# Power.net
KiCad netlist of a schematic drawn in Altium Designer
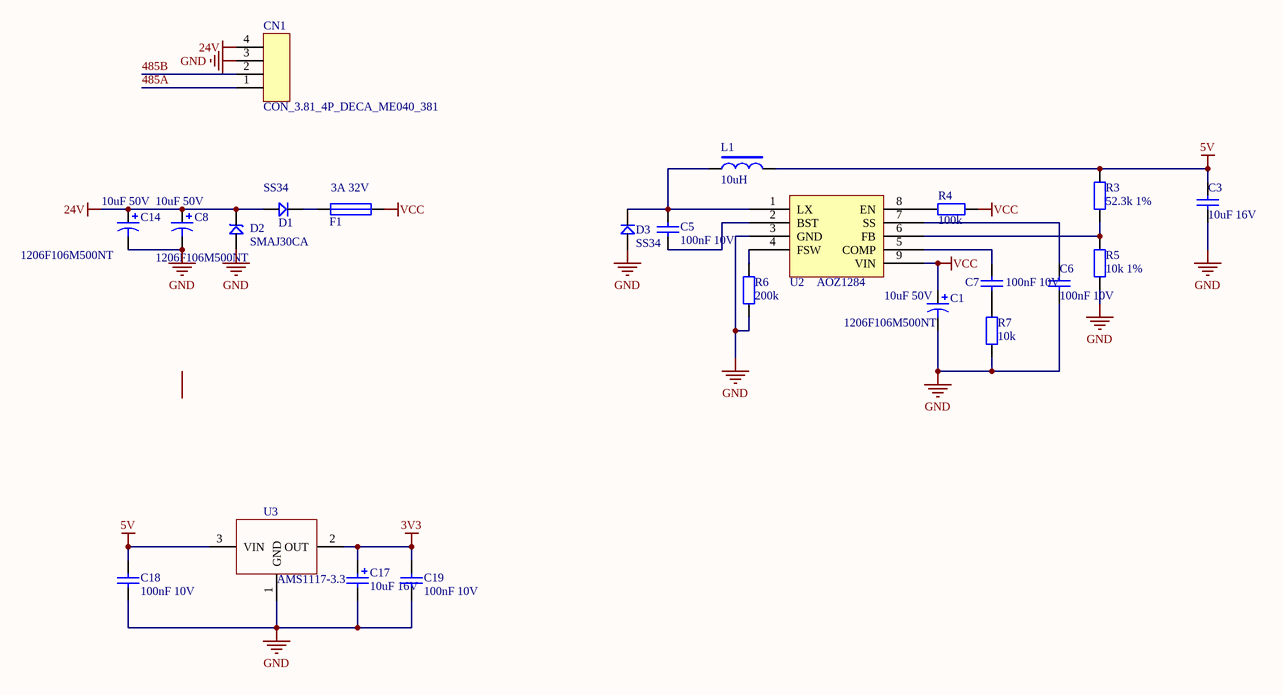
[diagram p0: Power.SchDoc]

(export (version "E")
  (design (tool "Eeschema 10.0.6"))
  (components
    (comp (ref "C1")
      (value "10uF 50V")
      (footprint "C1206")
      (description "贴片陶瓷电容")
      (fields (field (name "蜜称") "1206F106M500NT") (field (name "PUBLISHER") "Altium Limited"))
      (libsource (lib "Skcl") (part "Cap Pol1"))
    )
    (comp (ref "C3")
      (value "10uF 16V")
      (footprint "C1206")
      (description "贴片陶瓷电容")
      (libsource (lib "stm32_s") (part "CAP"))
    )
    (comp (ref "C5") (value "100nF 10V") (footprint "C0603") (libsource (lib "stm32_s") (part "CAP")))
    (comp (ref "C6") (value "100nF 10V") (footprint "C0603") (libsource (lib "stm32_s") (part "CAP")))
    (comp (ref "C7") (value "100nF 10V") (footprint "C0603") (libsource (lib "stm32_s") (part "CAP")))
    (comp (ref "C8")
      (value "10uF 50V")
      (footprint "C1206")
      (description "贴片陶瓷电容")
      (fields (field (name "蜜称") "1206F106M500NT") (field (name "PUBLISHER") "Altium Limited"))
      (libsource (lib "Skcl") (part "Cap Pol1"))
    )
    (comp (ref "C14")
      (value "10uF 50V")
      (footprint "C1206")
      (description "贴片陶瓷电容")
      (fields (field (name "蜜称") "1206F106M500NT") (field (name "PUBLISHER") "Altium Limited"))
      (libsource (lib "Skcl") (part "Cap Pol1"))
    )
    (comp (ref "C17")
      (value "10uF 16V")
      (footprint "C1206")
      (description "贴片陶瓷电容")
      (libsource (lib "stm32_s") (part "CAP1"))
    )
    (comp (ref "C18") (value "100nF 10V") (footprint "C0603") (libsource (lib "stm32_s") (part "CAP")))
    (comp (ref "C19") (value "100nF 10V") (footprint "C0603") (libsource (lib "stm32_s") (part "CAP")))
    (comp (ref "CN1")
      (value "CON_3.81_4P_DECA_ME040_381")
      (footprint "ME040_381_4P_VC-1")
      (description "DECA connector,3.81mm,1*4P,180度")
      (fields (field (name "MANUFACTURER") "DECA") (field (name "PARTNUMBER") "ME040-381-4P"))
      (libsource (lib "Schlib1") (part "CON_3.81_4P_DECA_ME040_381"))
    )
    (comp (ref "D1") (value "SS34") (footprint "LC-SMA(DO-214AC)_S3") (libsource (lib "stm32_s") (part "D")))
    (comp (ref "D2")
      (value "SMAJ30CA")
      (footprint "LC-SMA(DO-214AC)_S3")
      (description "TVS")
      (libsource (lib "stm32_s") (part "SMBJ"))
    )
    (comp (ref "D3") (value "SS34") (footprint "LC-SMA(DO-214AC)_S3") (libsource (lib "stm32_s") (part "D")))
    (comp (ref "F1") (value "3A 32V") (footprint "C1206") (libsource (lib "库") (part "FUSE")))
    (comp (ref "L1")
      (value "10uH")
      (footprint "L_SOP74")
      (description "贴片电感7*7mm")
      (libsource (lib "库") (part "差模电感"))
    )
    (comp (ref "R3") (value "52.3k 1%") (footprint "R0603") (libsource (lib "stm32_s") (part "RES")))
    (comp (ref "R4") (value "100k") (footprint "R0603") (libsource (lib "") (part "RES_1")))
    (comp (ref "R5") (value "10k 1%") (footprint "R0603") (libsource (lib "stm32_s") (part "RES")))
    (comp (ref "R6") (value "200k") (footprint "R0603") (libsource (lib "stm32_s") (part "RES")))
    (comp (ref "R7") (value "10k") (footprint "R0603") (libsource (lib "stm32_s") (part "RES")))
    (comp (ref "U2") (value "AOZ1284") (footprint "LC-SOP-8_150mil") (libsource (lib "库") (part "AOZ1284")))
    (comp (ref "U3") (value "AMS1117-3.3") (footprint "LT1117") (libsource (lib "stm32_s") (part "LT1117")))
  )
  (nets
    (net (code "1") (name "/485A") (class "Default")
      (node (ref "CN1") (pin "1") (pinfunction "1_1") (pintype "passive"))
    )
    (net (code "2") (name "/485B") (class "Default")
      (node (ref "CN1") (pin "2") (pinfunction "2_2") (pintype "passive"))
    )
    (net (code "3") (name "3V3") (class "Default")
      (node (ref "C17") (pin "1") (pinfunction "1_1") (pintype "passive"))
      (node (ref "C19") (pin "2") (pinfunction "2_2") (pintype "passive"))
      (node (ref "U3") (pin "2") (pinfunction "OUT_2") (pintype "passive"))
    )
    (net (code "4") (name "5V") (class "Default")
      (node (ref "C18") (pin "2") (pinfunction "2_2") (pintype "passive"))
      (node (ref "C3") (pin "1") (pinfunction "1_1") (pintype "passive"))
      (node (ref "L1") (pin "2") (pinfunction "2_2") (pintype "passive"))
      (node (ref "R3") (pin "2") (pinfunction "2_2") (pintype "passive"))
      (node (ref "U3") (pin "3") (pinfunction "VIN_3") (pintype "passive"))
    )
    (net (code "5") (name "24V") (class "Default")
      (node (ref "C14") (pin "1") (pinfunction "1_1") (pintype "passive"))
      (node (ref "C8") (pin "1") (pinfunction "1_1") (pintype "passive"))
      (node (ref "CN1") (pin "4") (pinfunction "4_4") (pintype "passive"))
      (node (ref "D1") (pin "1") (pintype "passive"))
      (node (ref "D2") (pin "2") (pintype "passive"))
    )
    (net (code "6") (name "GND") (class "Default")
      (node (ref "C1") (pin "2") (pinfunction "2_2") (pintype "passive"))
      (node (ref "C14") (pin "2") (pinfunction "2_2") (pintype "passive"))
      (node (ref "C17") (pin "2") (pinfunction "2_2") (pintype "passive"))
      (node (ref "C18") (pin "1") (pinfunction "1_1") (pintype "passive"))
      (node (ref "C19") (pin "1") (pinfunction "1_1") (pintype "passive"))
      (node (ref "C3") (pin "2") (pinfunction "2_2") (pintype "passive"))
      (node (ref "C6") (pin "2") (pinfunction "2_2") (pintype "passive"))
      (node (ref "C8") (pin "2") (pinfunction "2_2") (pintype "passive"))
      (node (ref "CN1") (pin "3") (pinfunction "3_3") (pintype "passive"))
      (node (ref "D2") (pin "1") (pintype "passive"))
      (node (ref "D3") (pin "1") (pintype "passive"))
      (node (ref "R5") (pin "1") (pinfunction "1_1") (pintype "passive"))
      (node (ref "R6") (pin "1") (pinfunction "1_1") (pintype "passive"))
      (node (ref "R7") (pin "1") (pinfunction "1_1") (pintype "passive"))
      (node (ref "U2") (pin "3") (pinfunction "GND_3") (pintype "passive"))
      (node (ref "U3") (pin "1") (pinfunction "GND_1") (pintype "passive"))
    )
    (net (code "7") (name "Net-(C7-Pad2)") (class "Default")
      (node (ref "C7") (pin "2") (pinfunction "2_2") (pintype "passive"))
      (node (ref "R7") (pin "2") (pinfunction "2_2") (pintype "passive"))
    )
    (net (code "8") (name "Net-(D1-Pad2)") (class "Default")
      (node (ref "D1") (pin "2") (pintype "passive"))
      (node (ref "F1") (pin "1") (pinfunction "1_1") (pintype "passive"))
    )
    (net (code "9") (name "Net-(U2-BST)") (class "Default")
      (node (ref "C5") (pin "1") (pinfunction "1_1") (pintype "passive"))
      (node (ref "U2") (pin "2") (pinfunction "BST_2") (pintype "passive"))
    )
    (net (code "10") (name "Net-(U2-COMP)") (class "Default")
      (node (ref "C7") (pin "1") (pinfunction "1_1") (pintype "passive"))
      (node (ref "U2") (pin "5") (pinfunction "COMP_5") (pintype "passive"))
    )
    (net (code "11") (name "Net-(U2-EN)") (class "Default")
      (node (ref "R4") (pin "1") (pinfunction "1_1") (pintype "passive"))
      (node (ref "U2") (pin "8") (pinfunction "EN_8") (pintype "passive"))
    )
    (net (code "12") (name "Net-(U2-FB)") (class "Default")
      (node (ref "R3") (pin "1") (pinfunction "1_1") (pintype "passive"))
      (node (ref "R5") (pin "2") (pinfunction "2_2") (pintype "passive"))
      (node (ref "U2") (pin "6") (pinfunction "FB_6") (pintype "passive"))
    )
    (net (code "13") (name "Net-(U2-FSW)") (class "Default")
      (node (ref "R6") (pin "2") (pinfunction "2_2") (pintype "passive"))
      (node (ref "U2") (pin "4") (pinfunction "FSW_4") (pintype "passive"))
    )
    (net (code "14") (name "Net-(U2-LX)") (class "Default")
      (node (ref "C5") (pin "2") (pinfunction "2_2") (pintype "passive"))
      (node (ref "D3") (pin "2") (pintype "passive"))
      (node (ref "L1") (pin "1") (pinfunction "1_1") (pintype "passive"))
      (node (ref "U2") (pin "1") (pinfunction "LX_1") (pintype "passive"))
    )
    (net (code "15") (name "Net-(U2-SS)") (class "Default")
      (node (ref "C6") (pin "1") (pinfunction "1_1") (pintype "passive"))
      (node (ref "U2") (pin "7") (pinfunction "SS_7") (pintype "passive"))
    )
    (net (code "16") (name "VCC") (class "Default")
      (node (ref "C1") (pin "1") (pinfunction "1_1") (pintype "passive"))
      (node (ref "F1") (pin "2") (pinfunction "2_2") (pintype "passive"))
      (node (ref "R4") (pin "2") (pinfunction "2_2") (pintype "passive"))
      (node (ref "U2") (pin "9") (pinfunction "VIN_9") (pintype "passive"))
    )
  )
)
